# PowerSocket2.net
KiCad netlist of a schematic drawn in EAGLE
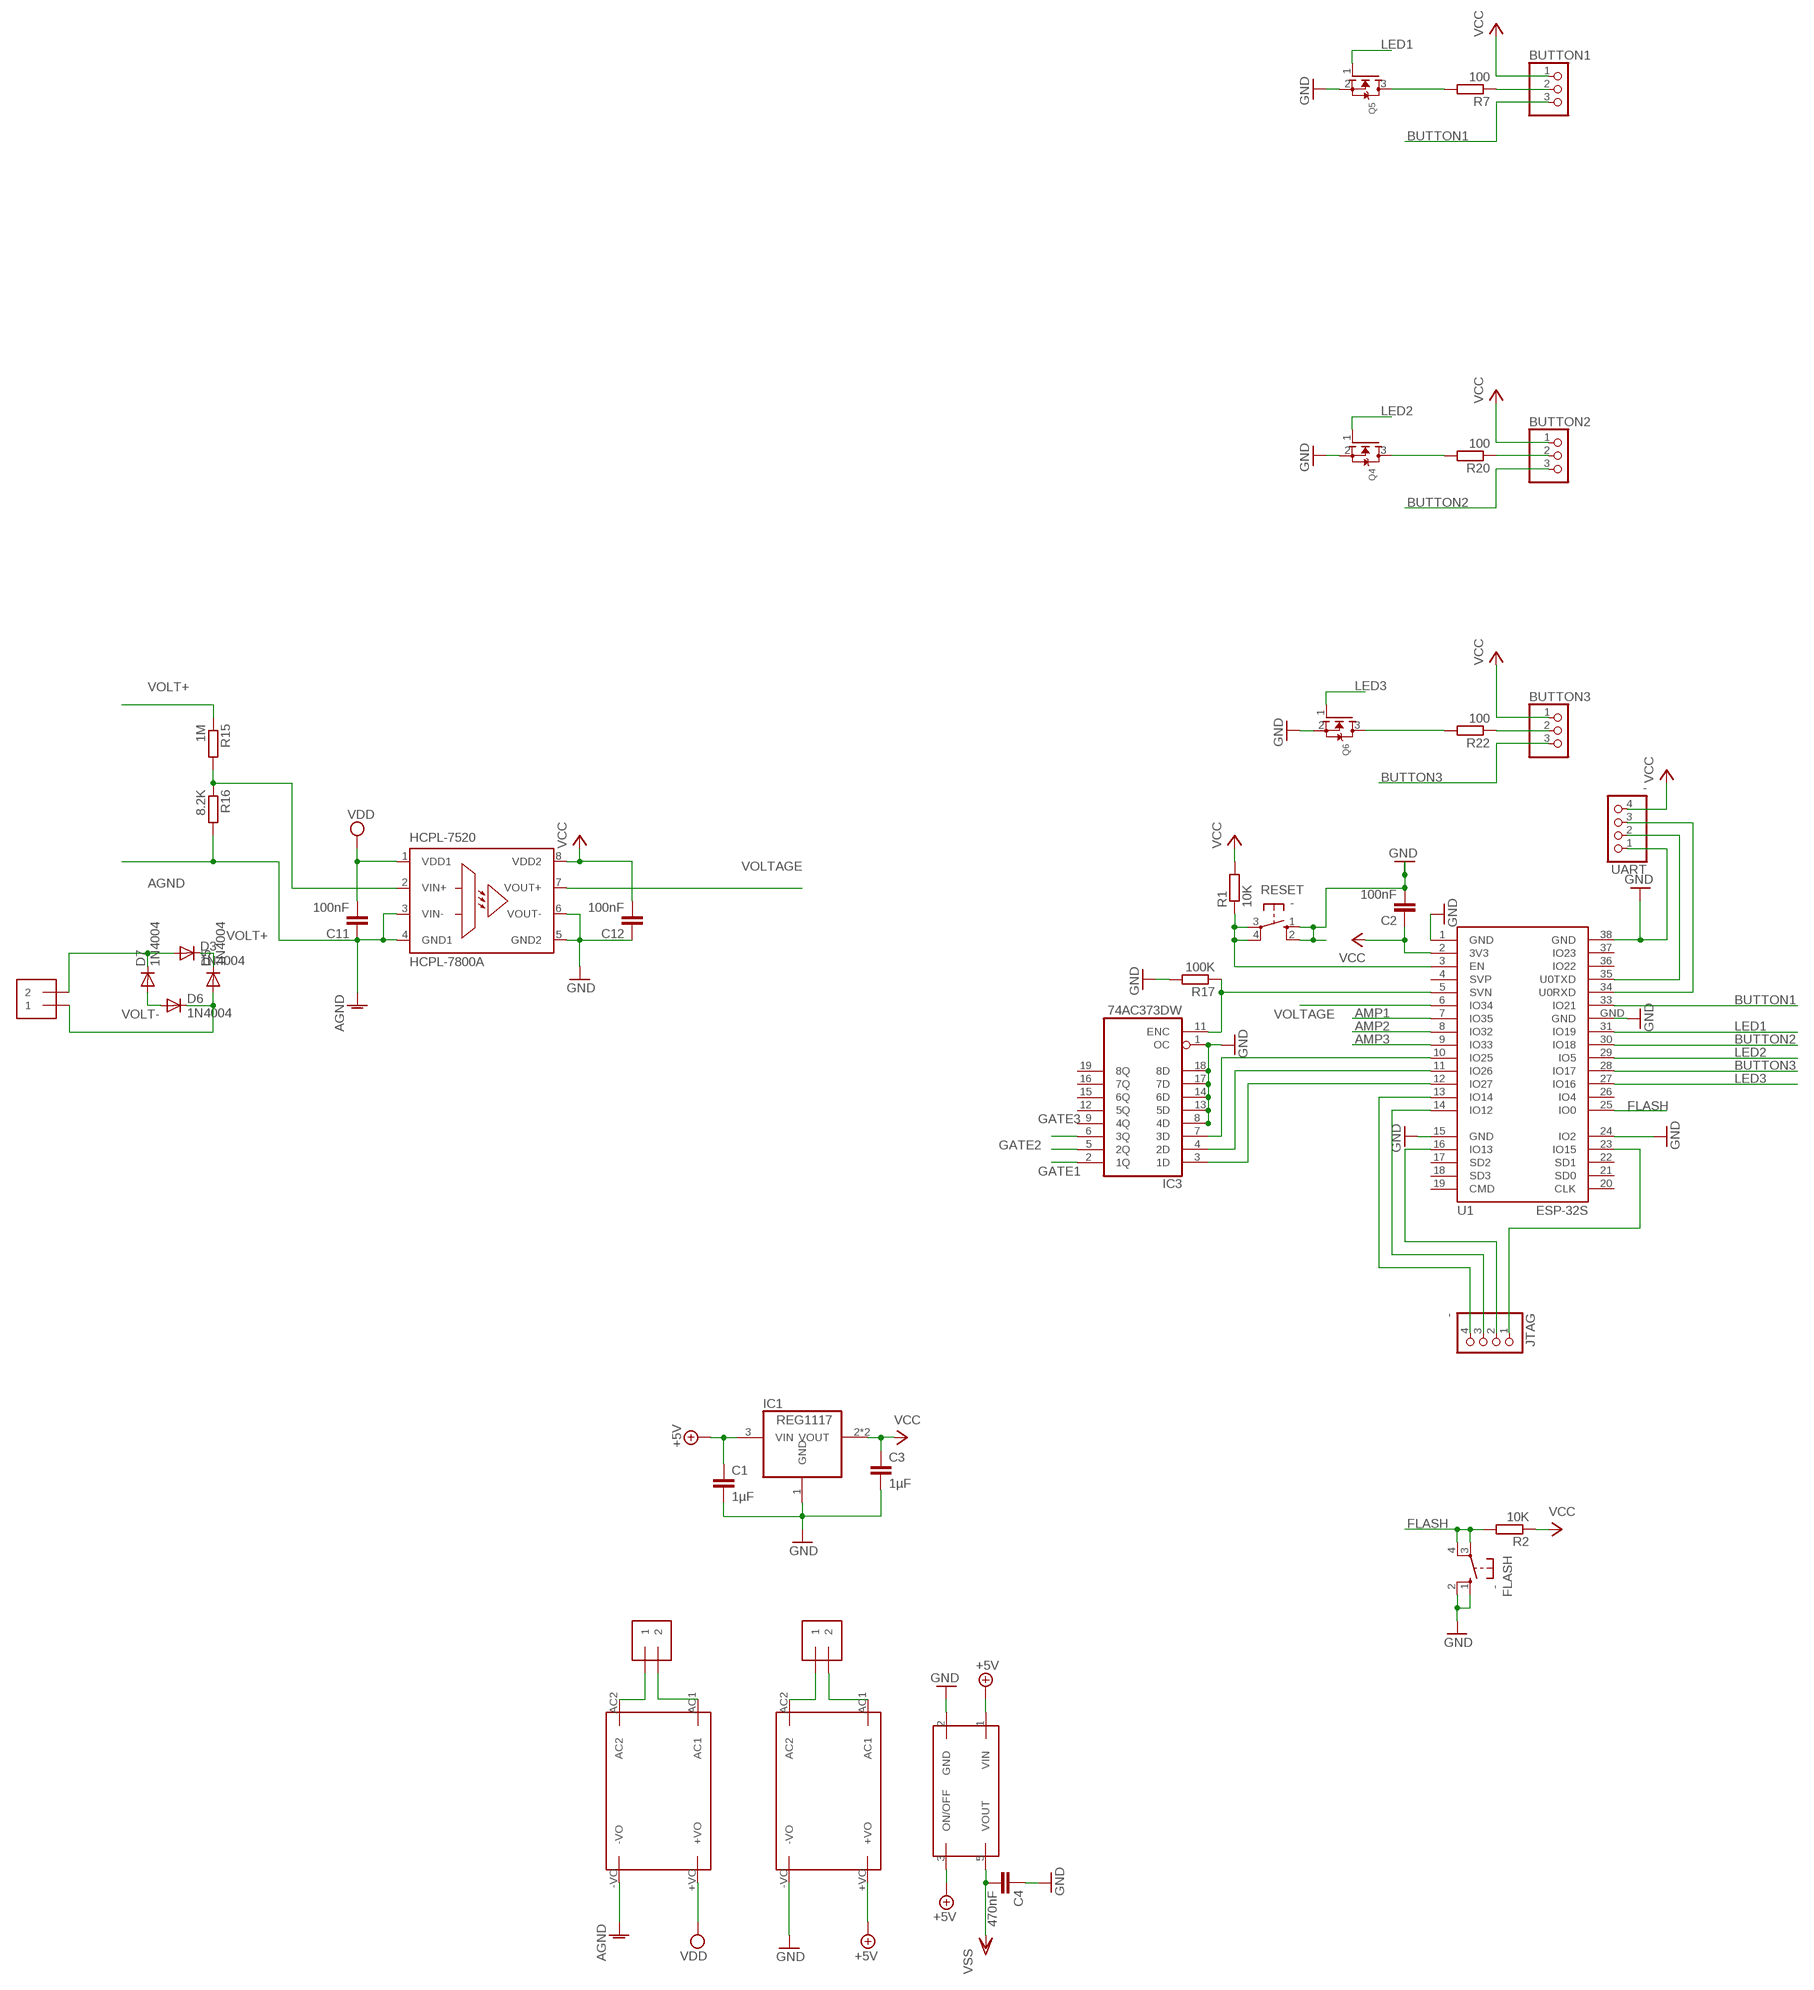
[diagram p0: schematic, sheet 1, part 1 of 2]
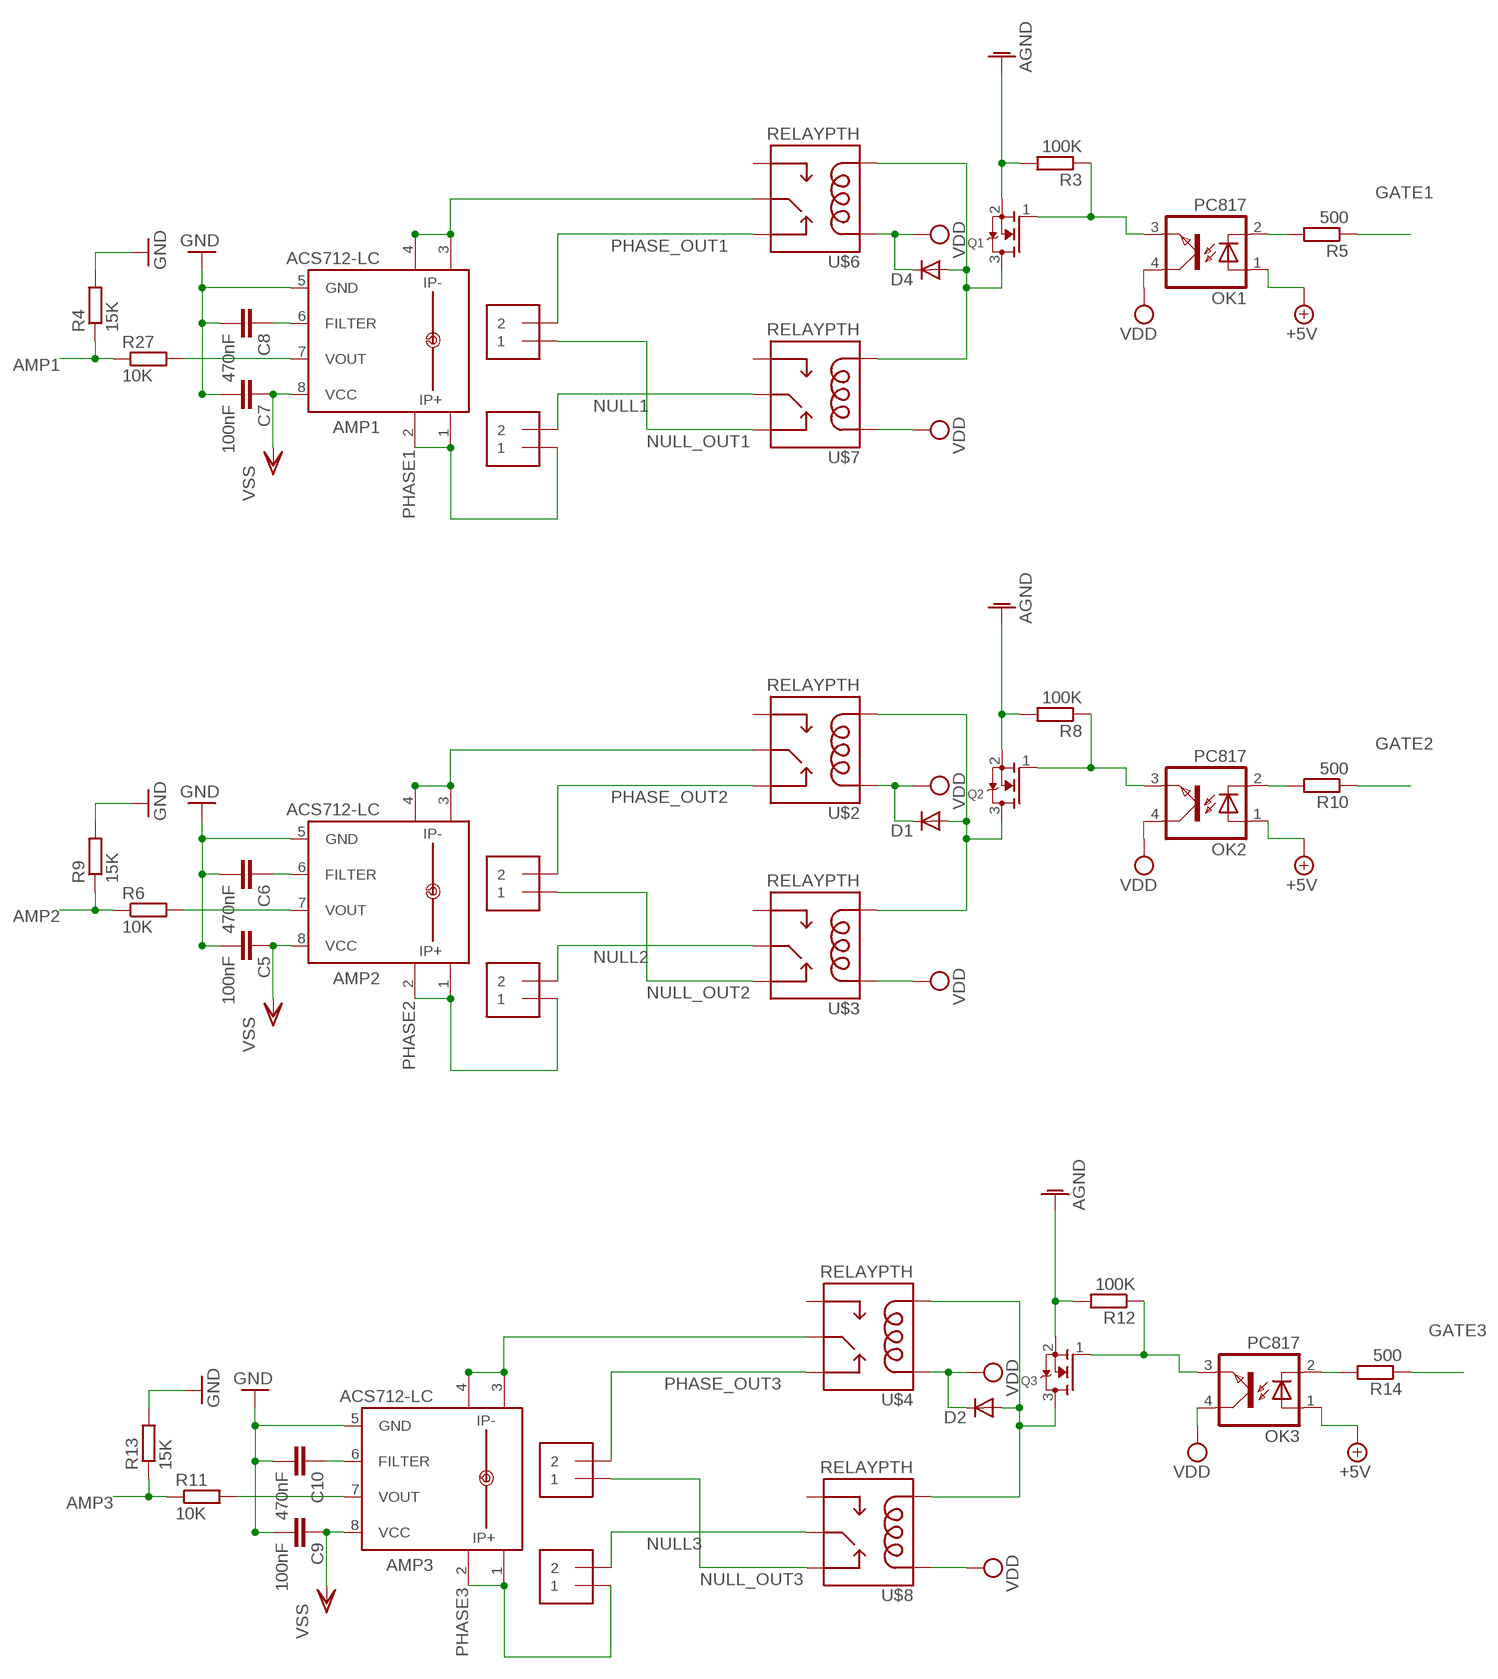
[diagram p1: schematic, sheet 1, part 2 of 2]

(export (version "E")
  (design (tool "Eeschema 10.0.6"))
  (components
    (comp (ref "4.5V_REG")
      (value "S1112")
      (footprint "eagle-import:SOT23-5")
      (libsource (lib "eagle-import") (part "S1112"))
    )
    (comp (ref "AMP1")
      (value "ACS712-LC")
      (footprint "eagle-import:SOIC8")
      (libsource (lib "eagle-import") (part "ACS712-LC"))
    )
    (comp (ref "AMP2")
      (value "ACS712-LC")
      (footprint "eagle-import:SOIC8")
      (libsource (lib "eagle-import") (part "ACS712-LC"))
    )
    (comp (ref "AMP3")
      (value "ACS712-LC")
      (footprint "eagle-import:SOIC8")
      (libsource (lib "eagle-import") (part "ACS712-LC"))
    )
    (comp (ref "BUTTON1")
      (value "PINHD-1X3")
      (footprint "eagle-import:1X03")
      (libsource (lib "eagle-import") (part "PINHD-1X3"))
    )
    (comp (ref "BUTTON2")
      (value "PINHD-1X3")
      (footprint "eagle-import:1X03")
      (libsource (lib "eagle-import") (part "PINHD-1X3"))
    )
    (comp (ref "BUTTON3")
      (value "PINHD-1X3")
      (footprint "eagle-import:1X03")
      (libsource (lib "eagle-import") (part "PINHD-1X3"))
    )
    (comp (ref "C1")
      (value "1µF")
      (footprint "eagle-import:C025-024X044")
      (libsource (lib "eagle-import") (part "C-EU025-024X044"))
    )
    (comp (ref "C2")
      (value "100nF")
      (footprint "eagle-import:C1206")
      (libsource (lib "eagle-import") (part "C-EUC1206"))
    )
    (comp (ref "C3")
      (value "1µF")
      (footprint "eagle-import:C025-024X044")
      (libsource (lib "eagle-import") (part "C-EU025-024X044"))
    )
    (comp (ref "C4")
      (value "470nF")
      (footprint "eagle-import:C0805")
      (libsource (lib "eagle-import") (part "C-EUC0805"))
    )
    (comp (ref "C5")
      (value "100nF")
      (footprint "eagle-import:C0805")
      (libsource (lib "eagle-import") (part "C-EUC0805"))
    )
    (comp (ref "C6")
      (value "470nF")
      (footprint "eagle-import:C0805")
      (libsource (lib "eagle-import") (part "C-EUC0805"))
    )
    (comp (ref "C7")
      (value "100nF")
      (footprint "eagle-import:C0805")
      (libsource (lib "eagle-import") (part "C-EUC0805"))
    )
    (comp (ref "C8")
      (value "470nF")
      (footprint "eagle-import:C0805")
      (libsource (lib "eagle-import") (part "C-EUC0805"))
    )
    (comp (ref "C9")
      (value "100nF")
      (footprint "eagle-import:C0805")
      (libsource (lib "eagle-import") (part "C-EUC0805"))
    )
    (comp (ref "C10")
      (value "470nF")
      (footprint "eagle-import:C0805")
      (libsource (lib "eagle-import") (part "C-EUC0805"))
    )
    (comp (ref "C11")
      (value "100nF")
      (footprint "eagle-import:C1206")
      (libsource (lib "eagle-import") (part "C-EUC1206"))
    )
    (comp (ref "C12")
      (value "100nF")
      (footprint "eagle-import:C1206")
      (libsource (lib "eagle-import") (part "C-EUC1206"))
    )
    (comp (ref "D1")
      (value "DIODE-DO-214AC")
      (footprint "eagle-import:DO-214AC")
      (libsource (lib "eagle-import") (part "DIODE-DO-214AC"))
    )
    (comp (ref "D2")
      (value "DIODE-DO-214AC")
      (footprint "eagle-import:DO-214AC")
      (libsource (lib "eagle-import") (part "DIODE-DO-214AC"))
    )
    (comp (ref "D3")
      (value "1N4004")
      (footprint "eagle-import:DO41-10")
      (libsource (lib "eagle-import") (part "1N4004"))
    )
    (comp (ref "D4")
      (value "DIODE-DO-214AC")
      (footprint "eagle-import:DO-214AC")
      (libsource (lib "eagle-import") (part "DIODE-DO-214AC"))
    )
    (comp (ref "D5")
      (value "1N4004")
      (footprint "eagle-import:DO41-10")
      (libsource (lib "eagle-import") (part "1N4004"))
    )
    (comp (ref "D6")
      (value "1N4004")
      (footprint "eagle-import:DO41-10")
      (libsource (lib "eagle-import") (part "1N4004"))
    )
    (comp (ref "D7")
      (value "1N4004")
      (footprint "eagle-import:DO41-10")
      (libsource (lib "eagle-import") (part "1N4004"))
    )
    (comp (ref "FLASH")
      (value "-")
      (footprint "eagle-import:B3F-10XX")
      (fields (field (name "MPN") "B3F-1000"))
      (libsource (lib "eagle-import") (part "10-XX"))
    )
    (comp (ref "HCPL-7520")
      (value "HCPL-7800A")
      (footprint "eagle-import:DIP8")
      (fields (field (name "MF") "AGILENT TECHNOLOGIES") (field (name "MPN") "HCPL-7800A-000E"))
      (libsource (lib "eagle-import") (part "HCPL-7800A"))
    )
    (comp (ref "IC1")
      (value "REG1117")
      (footprint "eagle-import:SOT223")
      (libsource (lib "eagle-import") (part "REG1117"))
    )
    (comp (ref "IC3")
      (value "74AC373DW")
      (footprint "eagle-import:SO20W")
      (libsource (lib "eagle-import") (part "74373DWAC"))
    )
    (comp (ref "J1")
      (value "1X2-3.5MM")
      (footprint "eagle-import:1X2-3.5MM")
      (libsource (lib "eagle-import") (part "1X2-3.5MM"))
    )
    (comp (ref "J2")
      (value "1X2-3.5MM")
      (footprint "eagle-import:1X2-3.5MM")
      (libsource (lib "eagle-import") (part "1X2-3.5MM"))
    )
    (comp (ref "J3")
      (value "1X2-3.5MM")
      (footprint "eagle-import:1X2-3.5MM")
      (libsource (lib "eagle-import") (part "1X2-3.5MM"))
    )
    (comp (ref "J4")
      (value "1X2-3.5MM")
      (footprint "eagle-import:1X2-3.5MM")
      (libsource (lib "eagle-import") (part "1X2-3.5MM"))
    )
    (comp (ref "J5")
      (value "1X2-3.5MM")
      (footprint "eagle-import:1X2-3.5MM")
      (libsource (lib "eagle-import") (part "1X2-3.5MM"))
    )
    (comp (ref "J6")
      (value "1X2-3.5MM")
      (footprint "eagle-import:1X2-3.5MM")
      (libsource (lib "eagle-import") (part "1X2-3.5MM"))
    )
    (comp (ref "J7")
      (value "1X2-3.5MM")
      (footprint "eagle-import:1X2-3.5MM")
      (libsource (lib "eagle-import") (part "1X2-3.5MM"))
    )
    (comp (ref "J8")
      (value "1X2-3.5MM")
      (footprint "eagle-import:1X2-3.5MM")
      (libsource (lib "eagle-import") (part "1X2-3.5MM"))
    )
    (comp (ref "J9")
      (value "1X2-3.5MM")
      (footprint "eagle-import:1X2-3.5MM")
      (libsource (lib "eagle-import") (part "1X2-3.5MM"))
    )
    (comp (ref "JTAG")
      (value "-")
      (footprint "eagle-import:1X04")
      (libsource (lib "eagle-import") (part "PINHD-1X4"))
    )
    (comp (ref "OK1")
      (value "PC817")
      (footprint "eagle-import:DIL04")
      (fields (field (name "MPN") "PC817X4J000F"))
      (libsource (lib "eagle-import") (part "PC817"))
    )
    (comp (ref "OK2")
      (value "PC817")
      (footprint "eagle-import:DIL04")
      (fields (field (name "MPN") "PC817X4J000F"))
      (libsource (lib "eagle-import") (part "PC817"))
    )
    (comp (ref "OK3")
      (value "PC817")
      (footprint "eagle-import:DIL04")
      (fields (field (name "MPN") "PC817X4J000F"))
      (libsource (lib "eagle-import") (part "PC817"))
    )
    (comp (ref "Q1")
      (value "MOSFET-NREFLOW")
      (footprint "eagle-import:SOT23")
      (libsource (lib "eagle-import") (part "MOSFET-NREFLOW"))
    )
    (comp (ref "Q2")
      (value "MOSFET-NREFLOW")
      (footprint "eagle-import:SOT23")
      (libsource (lib "eagle-import") (part "MOSFET-NREFLOW"))
    )
    (comp (ref "Q3")
      (value "MOSFET-NREFLOW")
      (footprint "eagle-import:SOT23")
      (libsource (lib "eagle-import") (part "MOSFET-NREFLOW"))
    )
    (comp (ref "Q4")
      (value "MOSFET-NREFLOW")
      (footprint "eagle-import:SOT23")
      (libsource (lib "eagle-import") (part "MOSFET-NREFLOW"))
    )
    (comp (ref "Q5")
      (value "MOSFET-NREFLOW")
      (footprint "eagle-import:SOT23")
      (libsource (lib "eagle-import") (part "MOSFET-NREFLOW"))
    )
    (comp (ref "Q6")
      (value "MOSFET-NREFLOW")
      (footprint "eagle-import:SOT23")
      (libsource (lib "eagle-import") (part "MOSFET-NREFLOW"))
    )
    (comp (ref "R1")
      (value "10K")
      (footprint "eagle-import:R0805")
      (libsource (lib "eagle-import") (part "R-EU_R0805"))
    )
    (comp (ref "R2")
      (value "10K")
      (footprint "eagle-import:R0805")
      (libsource (lib "eagle-import") (part "R-EU_R0805"))
    )
    (comp (ref "R3")
      (value "100K")
      (footprint "eagle-import:R0805")
      (libsource (lib "eagle-import") (part "R-EU_R0805"))
    )
    (comp (ref "R4")
      (value "15K")
      (footprint "eagle-import:R0805")
      (libsource (lib "eagle-import") (part "R-EU_R0805"))
    )
    (comp (ref "R5")
      (value "500")
      (footprint "eagle-import:R0805")
      (libsource (lib "eagle-import") (part "R-EU_R0805"))
    )
    (comp (ref "R6")
      (value "10K")
      (footprint "eagle-import:R0805")
      (libsource (lib "eagle-import") (part "R-EU_R0805"))
    )
    (comp (ref "R7")
      (value "100")
      (footprint "eagle-import:R0805")
      (libsource (lib "eagle-import") (part "R-EU_R0805"))
    )
    (comp (ref "R8")
      (value "100K")
      (footprint "eagle-import:R0805")
      (libsource (lib "eagle-import") (part "R-EU_R0805"))
    )
    (comp (ref "R9")
      (value "15K")
      (footprint "eagle-import:R0805")
      (libsource (lib "eagle-import") (part "R-EU_R0805"))
    )
    (comp (ref "R10")
      (value "500")
      (footprint "eagle-import:R0805")
      (libsource (lib "eagle-import") (part "R-EU_R0805"))
    )
    (comp (ref "R11")
      (value "10K")
      (footprint "eagle-import:R0805")
      (libsource (lib "eagle-import") (part "R-EU_R0805"))
    )
    (comp (ref "R12")
      (value "100K")
      (footprint "eagle-import:R0805")
      (libsource (lib "eagle-import") (part "R-EU_R0805"))
    )
    (comp (ref "R13")
      (value "15K")
      (footprint "eagle-import:R0805")
      (libsource (lib "eagle-import") (part "R-EU_R0805"))
    )
    (comp (ref "R14")
      (value "500")
      (footprint "eagle-import:R0805")
      (libsource (lib "eagle-import") (part "R-EU_R0805"))
    )
    (comp (ref "R15")
      (value "1M")
      (footprint "eagle-import:0207_10")
      (libsource (lib "eagle-import") (part "resistor_R-EU_0207/10"))
    )
    (comp (ref "R16")
      (value "8.2K")
      (footprint "eagle-import:0207_10")
      (libsource (lib "eagle-import") (part "resistor_R-EU_0207/10"))
    )
    (comp (ref "R17")
      (value "100K")
      (footprint "eagle-import:R0805")
      (libsource (lib "eagle-import") (part "R-EU_R0805"))
    )
    (comp (ref "R20")
      (value "100")
      (footprint "eagle-import:R0805")
      (libsource (lib "eagle-import") (part "R-EU_R0805"))
    )
    (comp (ref "R22")
      (value "100")
      (footprint "eagle-import:R0805")
      (libsource (lib "eagle-import") (part "R-EU_R0805"))
    )
    (comp (ref "R27")
      (value "10K")
      (footprint "eagle-import:R0805")
      (libsource (lib "eagle-import") (part "R-EU_R0805"))
    )
    (comp (ref "RESET")
      (value "-")
      (footprint "eagle-import:B3F-10XX")
      (fields (field (name "MPN") "B3F-1000"))
      (libsource (lib "eagle-import") (part "10-XX"))
    )
    (comp (ref "U$1")
      (value "HLK-PM03")
      (footprint "eagle-import:HLK-PM03")
      (libsource (lib "eagle-import") (part "HLK-PM03"))
    )
    (comp (ref "U$2")
      (value "RELAYPTH")
      (footprint "eagle-import:SRD-05VDC-SL-C")
      (libsource (lib "eagle-import") (part "RELAYPTH"))
    )
    (comp (ref "U$3")
      (value "RELAYPTH")
      (footprint "eagle-import:SRD-05VDC-SL-C")
      (libsource (lib "eagle-import") (part "RELAYPTH"))
    )
    (comp (ref "U$4")
      (value "RELAYPTH")
      (footprint "eagle-import:SRD-05VDC-SL-C")
      (libsource (lib "eagle-import") (part "RELAYPTH"))
    )
    (comp (ref "U$5")
      (value "HLK-PM03")
      (footprint "eagle-import:HLK-PM03")
      (libsource (lib "eagle-import") (part "HLK-PM03"))
    )
    (comp (ref "U$6")
      (value "RELAYPTH")
      (footprint "eagle-import:SRD-05VDC-SL-C")
      (libsource (lib "eagle-import") (part "RELAYPTH"))
    )
    (comp (ref "U$7")
      (value "RELAYPTH")
      (footprint "eagle-import:SRD-05VDC-SL-C")
      (libsource (lib "eagle-import") (part "RELAYPTH"))
    )
    (comp (ref "U$8")
      (value "RELAYPTH")
      (footprint "eagle-import:SRD-05VDC-SL-C")
      (libsource (lib "eagle-import") (part "RELAYPTH"))
    )
    (comp (ref "U1")
      (value "ESP-32S")
      (footprint "eagle-import:ESP-32S")
      (libsource (lib "eagle-import") (part "ESP-32S"))
    )
    (comp (ref "UART")
      (value "-")
      (footprint "eagle-import:1X04")
      (libsource (lib "eagle-import") (part "PINHD-1X4"))
    )
  )
  (nets
    (net (code "1") (name "+5V") (class "Default")
      (node (ref "4.5V_REG") (pin "1") (pinfunction "VIN_1") (pintype "power_in"))
      (node (ref "4.5V_REG") (pin "3") (pinfunction "ON/OFF_3") (pintype "input"))
      (node (ref "C1") (pin "1") (pinfunction "1_1") (pintype "passive"))
      (node (ref "IC1") (pin "3") (pinfunction "VIN_3") (pintype "input"))
      (node (ref "OK1") (pin "1") (pinfunction "A_1") (pintype "passive"))
      (node (ref "OK2") (pin "1") (pinfunction "A_1") (pintype "passive"))
      (node (ref "OK3") (pin "1") (pinfunction "A_1") (pintype "passive"))
      (node (ref "U$1") (pin "+VO") (pinfunction "+VO_+VO") (pintype "bidirectional"))
    )
    (net (code "2") (name "/AMP1") (class "Default")
      (node (ref "R27") (pin "1") (pinfunction "1_1") (pintype "passive"))
      (node (ref "R4") (pin "1") (pinfunction "1_1") (pintype "passive"))
      (node (ref "U1") (pin "7") (pinfunction "IO35_7") (pintype "bidirectional"))
    )
    (net (code "3") (name "/AMP2") (class "Default")
      (node (ref "R6") (pin "1") (pinfunction "1_1") (pintype "passive"))
      (node (ref "R9") (pin "1") (pinfunction "1_1") (pintype "passive"))
      (node (ref "U1") (pin "8") (pinfunction "IO32_8") (pintype "bidirectional"))
    )
    (net (code "4") (name "/AMP3") (class "Default")
      (node (ref "R11") (pin "1") (pinfunction "1_1") (pintype "passive"))
      (node (ref "R13") (pin "1") (pinfunction "1_1") (pintype "passive"))
      (node (ref "U1") (pin "9") (pinfunction "IO33_9") (pintype "bidirectional"))
    )
    (net (code "5") (name "/BUTTON1") (class "Default")
      (node (ref "BUTTON1") (pin "3") (pinfunction "3_3") (pintype "passive"))
      (node (ref "U1") (pin "33") (pinfunction "IO21_33") (pintype "bidirectional"))
    )
    (net (code "6") (name "/BUTTON2") (class "Default")
      (node (ref "BUTTON2") (pin "3") (pinfunction "3_3") (pintype "passive"))
      (node (ref "U1") (pin "30") (pinfunction "IO18_30") (pintype "bidirectional"))
    )
    (net (code "7") (name "/BUTTON3") (class "Default")
      (node (ref "BUTTON3") (pin "3") (pinfunction "3_3") (pintype "passive"))
      (node (ref "U1") (pin "28") (pinfunction "IO17_28") (pintype "bidirectional"))
    )
    (net (code "8") (name "/FLASH") (class "Default")
      (node (ref "FLASH") (pin "3") (pinfunction "P_3") (pintype "passive"))
      (node (ref "FLASH") (pin "4") (pinfunction "P1_4") (pintype "passive"))
      (node (ref "R2") (pin "2") (pinfunction "2_2") (pintype "passive"))
      (node (ref "U1") (pin "25") (pinfunction "IO0_25") (pintype "bidirectional"))
    )
    (net (code "9") (name "/GATE1") (class "Default")
      (node (ref "IC3") (pin "2") (pinfunction "1Q_2") (pintype "tri_state"))
      (node (ref "R5") (pin "1") (pinfunction "1_1") (pintype "passive"))
    )
    (net (code "10") (name "/GATE2") (class "Default")
      (node (ref "IC3") (pin "5") (pinfunction "2Q_5") (pintype "tri_state"))
      (node (ref "R10") (pin "1") (pinfunction "1_1") (pintype "passive"))
    )
    (net (code "11") (name "/GATE3") (class "Default")
      (node (ref "IC3") (pin "6") (pinfunction "3Q_6") (pintype "tri_state"))
      (node (ref "R14") (pin "1") (pinfunction "1_1") (pintype "passive"))
    )
    (net (code "12") (name "/LED1") (class "Default")
      (node (ref "Q5") (pin "1") (pinfunction "G_1") (pintype "bidirectional"))
      (node (ref "U1") (pin "31") (pinfunction "IO19_31") (pintype "bidirectional"))
    )
    (net (code "13") (name "/LED2") (class "Default")
      (node (ref "Q4") (pin "1") (pinfunction "G_1") (pintype "bidirectional"))
      (node (ref "U1") (pin "29") (pinfunction "IO5_29") (pintype "bidirectional"))
    )
    (net (code "14") (name "/LED3") (class "Default")
      (node (ref "Q6") (pin "1") (pinfunction "G_1") (pintype "bidirectional"))
      (node (ref "U1") (pin "27") (pinfunction "IO16_27") (pintype "bidirectional"))
    )
    (net (code "15") (name "/NULL1") (class "Default")
      (node (ref "J2") (pin "2") (pinfunction "2_2") (pintype "passive"))
      (node (ref "U$7") (pin "SWCOMMON") (pinfunction "SWCOMMON_SWCOMMON") (pintype "bidirectional"))
    )
    (net (code "16") (name "/NULL2") (class "Default")
      (node (ref "J6") (pin "2") (pinfunction "2_2") (pintype "passive"))
      (node (ref "U$3") (pin "SWCOMMON") (pinfunction "SWCOMMON_SWCOMMON") (pintype "bidirectional"))
    )
    (net (code "17") (name "/NULL3") (class "Default")
      (node (ref "J8") (pin "2") (pinfunction "2_2") (pintype "passive"))
      (node (ref "U$8") (pin "SWCOMMON") (pinfunction "SWCOMMON_SWCOMMON") (pintype "bidirectional"))
    )
    (net (code "18") (name "/NULL_OUT1") (class "Default")
      (node (ref "J1") (pin "1") (pinfunction "1_1") (pintype "passive"))
      (node (ref "U$7") (pin "SWCLOSED") (pinfunction "SWCLOSE_SWCLOSED") (pintype "bidirectional"))
    )
    (net (code "19") (name "/NULL_OUT2") (class "Default")
      (node (ref "J5") (pin "1") (pinfunction "1_1") (pintype "passive"))
      (node (ref "U$3") (pin "SWCLOSED") (pinfunction "SWCLOSE_SWCLOSED") (pintype "bidirectional"))
    )
    (net (code "20") (name "/NULL_OUT3") (class "Default")
      (node (ref "J7") (pin "1") (pinfunction "1_1") (pintype "passive"))
      (node (ref "U$8") (pin "SWCLOSED") (pinfunction "SWCLOSE_SWCLOSED") (pintype "bidirectional"))
    )
    (net (code "21") (name "/PHASE1") (class "Default")
      (node (ref "AMP1") (pin "1") (pinfunction "IP+_1") (pintype "passive"))
      (node (ref "AMP1") (pin "2") (pinfunction "IP+1_2") (pintype "passive"))
      (node (ref "J2") (pin "1") (pinfunction "1_1") (pintype "passive"))
    )
    (net (code "22") (name "/PHASE2") (class "Default")
      (node (ref "AMP2") (pin "1") (pinfunction "IP+_1") (pintype "passive"))
      (node (ref "AMP2") (pin "2") (pinfunction "IP+1_2") (pintype "passive"))
      (node (ref "J6") (pin "1") (pinfunction "1_1") (pintype "passive"))
    )
    (net (code "23") (name "/PHASE3") (class "Default")
      (node (ref "AMP3") (pin "1") (pinfunction "IP+_1") (pintype "passive"))
      (node (ref "AMP3") (pin "2") (pinfunction "IP+1_2") (pintype "passive"))
      (node (ref "J8") (pin "1") (pinfunction "1_1") (pintype "passive"))
    )
    (net (code "24") (name "/PHASE_OUT1") (class "Default")
      (node (ref "J1") (pin "2") (pinfunction "2_2") (pintype "passive"))
      (node (ref "U$6") (pin "SWCLOSED") (pinfunction "SWCLOSE_SWCLOSED") (pintype "bidirectional"))
    )
    (net (code "25") (name "/PHASE_OUT2") (class "Default")
      (node (ref "J5") (pin "2") (pinfunction "2_2") (pintype "passive"))
      (node (ref "U$2") (pin "SWCLOSED") (pinfunction "SWCLOSE_SWCLOSED") (pintype "bidirectional"))
    )
    (net (code "26") (name "/PHASE_OUT3") (class "Default")
      (node (ref "J7") (pin "2") (pinfunction "2_2") (pintype "passive"))
      (node (ref "U$4") (pin "SWCLOSED") (pinfunction "SWCLOSE_SWCLOSED") (pintype "bidirectional"))
    )
    (net (code "27") (name "/VOLT+") (class "Default")
      (node (ref "D3") (pin "C") (pinfunction "C_C") (pintype "passive"))
      (node (ref "D5") (pin "C") (pinfunction "C_C") (pintype "passive"))
      (node (ref "R15") (pin "1") (pinfunction "1_1") (pintype "passive"))
    )
    (net (code "28") (name "/VOLT-") (class "Default")
      (node (ref "D6") (pin "A") (pinfunction "A_A") (pintype "passive"))
      (node (ref "D7") (pin "A") (pinfunction "A_A") (pintype "passive"))
    )
    (net (code "29") (name "/VOLTAGE") (class "Default")
      (node (ref "HCPL-7520") (pin "7") (pinfunction "VOUT+_7") (pintype "power_in"))
      (node (ref "U1") (pin "6") (pinfunction "IO34_6") (pintype "bidirectional"))
    )
    (net (code "30") (name "AGND") (class "Default")
      (node (ref "C11") (pin "1") (pinfunction "1_1") (pintype "passive"))
      (node (ref "HCPL-7520") (pin "3") (pinfunction "VIN-_3") (pintype "power_in"))
      (node (ref "HCPL-7520") (pin "4") (pinfunction "GND1_4") (pintype "power_in"))
      (node (ref "Q1") (pin "2") (pinfunction "S_2") (pintype "bidirectional"))
      (node (ref "Q2") (pin "2") (pinfunction "S_2") (pintype "bidirectional"))
      (node (ref "Q3") (pin "2") (pinfunction "S_2") (pintype "bidirectional"))
      (node (ref "R12") (pin "2") (pinfunction "2_2") (pintype "passive"))
      (node (ref "R16") (pin "2") (pinfunction "2_2") (pintype "passive"))
      (node (ref "R3") (pin "2") (pinfunction "2_2") (pintype "passive"))
      (node (ref "R8") (pin "2") (pinfunction "2_2") (pintype "passive"))
      (node (ref "U$5") (pin "-VO") (pinfunction "-VO_-VO") (pintype "bidirectional"))
    )
    (net (code "31") (name "GND") (class "Default")
      (node (ref "4.5V_REG") (pin "2") (pinfunction "GND_2") (pintype "power_in"))
      (node (ref "AMP1") (pin "5") (pinfunction "GND_5") (pintype "power_in"))
      (node (ref "AMP2") (pin "5") (pinfunction "GND_5") (pintype "power_in"))
      (node (ref "AMP3") (pin "5") (pinfunction "GND_5") (pintype "power_in"))
      (node (ref "C1") (pin "2") (pinfunction "2_2") (pintype "passive"))
      (node (ref "C10") (pin "2") (pinfunction "2_2") (pintype "passive"))
      (node (ref "C12") (pin "1") (pinfunction "1_1") (pintype "passive"))
      (node (ref "C2") (pin "2") (pinfunction "2_2") (pintype "passive"))
      (node (ref "C3") (pin "2") (pinfunction "2_2") (pintype "passive"))
      (node (ref "C4") (pin "1") (pinfunction "1_1") (pintype "passive"))
      (node (ref "C5") (pin "2") (pinfunction "2_2") (pintype "passive"))
      (node (ref "C6") (pin "2") (pinfunction "2_2") (pintype "passive"))
      (node (ref "C7") (pin "2") (pinfunction "2_2") (pintype "passive"))
      (node (ref "C8") (pin "2") (pinfunction "2_2") (pintype "passive"))
      (node (ref "C9") (pin "2") (pinfunction "2_2") (pintype "passive"))
      (node (ref "FLASH") (pin "1") (pinfunction "S_1") (pintype "passive"))
      (node (ref "FLASH") (pin "2") (pinfunction "S1_2") (pintype "passive"))
      (node (ref "HCPL-7520") (pin "5") (pinfunction "GND2_5") (pintype "power_in"))
      (node (ref "HCPL-7520") (pin "6") (pinfunction "VOUT-_6") (pintype "power_in"))
      (node (ref "IC1") (pin "1") (pinfunction "GND_1") (pintype "power_in"))
      (node (ref "IC3") (pin "1") (pinfunction "OC_1") (pintype "input"))
      (node (ref "IC3") (pin "13") (pinfunction "5D_13") (pintype "input"))
      (node (ref "IC3") (pin "14") (pinfunction "6D_14") (pintype "input"))
      (node (ref "IC3") (pin "17") (pinfunction "7D_17") (pintype "input"))
      (node (ref "IC3") (pin "18") (pinfunction "8D_18") (pintype "input"))
      (node (ref "IC3") (pin "8") (pinfunction "4D_8") (pintype "input"))
      (node (ref "Q4") (pin "2") (pinfunction "S_2") (pintype "bidirectional"))
      (node (ref "Q5") (pin "2") (pinfunction "S_2") (pintype "bidirectional"))
      (node (ref "Q6") (pin "2") (pinfunction "S_2") (pintype "bidirectional"))
      (node (ref "R13") (pin "2") (pinfunction "2_2") (pintype "passive"))
      (node (ref "R17") (pin "2") (pinfunction "2_2") (pintype "passive"))
      (node (ref "R4") (pin "2") (pinfunction "2_2") (pintype "passive"))
      (node (ref "R9") (pin "2") (pinfunction "2_2") (pintype "passive"))
      (node (ref "RESET") (pin "1") (pinfunction "S_1") (pintype "passive"))
      (node (ref "RESET") (pin "2") (pinfunction "S1_2") (pintype "passive"))
      (node (ref "U$1") (pin "-VO") (pinfunction "-VO_-VO") (pintype "bidirectional"))
      (node (ref "U1") (pin "1") (pinfunction "GND_1") (pintype "power_in"))
      (node (ref "U1") (pin "15") (pinfunction "GND_15") (pintype "power_in"))
      (node (ref "U1") (pin "24") (pinfunction "IO2_24") (pintype "bidirectional"))
      (node (ref "U1") (pin "38") (pinfunction "GND_38") (pintype "power_in"))
      (node (ref "U1") (pin "GND") (pinfunction "GND_GND") (pintype "power_in"))
      (node (ref "UART") (pin "1") (pinfunction "1_1") (pintype "passive"))
    )
    (net (code "32") (name "Net-(AMP1-FILTER)") (class "Default")
      (node (ref "AMP1") (pin "6") (pinfunction "FILTER_6") (pintype "bidirectional"))
      (node (ref "C8") (pin "1") (pinfunction "1_1") (pintype "passive"))
    )
    (net (code "33") (name "Net-(AMP1-IP-)") (class "Default")
      (node (ref "AMP1") (pin "3") (pinfunction "IP-_3") (pintype "passive"))
      (node (ref "AMP1") (pin "4") (pinfunction "IP-1_4") (pintype "passive"))
      (node (ref "U$6") (pin "SWCOMMON") (pinfunction "SWCOMMON_SWCOMMON") (pintype "bidirectional"))
    )
    (net (code "34") (name "Net-(AMP1-VOUT)") (class "Default")
      (node (ref "AMP1") (pin "7") (pinfunction "VOUT_7") (pintype "output"))
      (node (ref "R27") (pin "2") (pinfunction "2_2") (pintype "passive"))
    )
    (net (code "35") (name "Net-(AMP2-FILTER)") (class "Default")
      (node (ref "AMP2") (pin "6") (pinfunction "FILTER_6") (pintype "bidirectional"))
      (node (ref "C6") (pin "1") (pinfunction "1_1") (pintype "passive"))
    )
    (net (code "36") (name "Net-(AMP2-IP-)") (class "Default")
      (node (ref "AMP2") (pin "3") (pinfunction "IP-_3") (pintype "passive"))
      (node (ref "AMP2") (pin "4") (pinfunction "IP-1_4") (pintype "passive"))
      (node (ref "U$2") (pin "SWCOMMON") (pinfunction "SWCOMMON_SWCOMMON") (pintype "bidirectional"))
    )
    (net (code "37") (name "Net-(AMP2-VOUT)") (class "Default")
      (node (ref "AMP2") (pin "7") (pinfunction "VOUT_7") (pintype "output"))
      (node (ref "R6") (pin "2") (pinfunction "2_2") (pintype "passive"))
    )
    (net (code "38") (name "Net-(AMP3-FILTER)") (class "Default")
      (node (ref "AMP3") (pin "6") (pinfunction "FILTER_6") (pintype "bidirectional"))
      (node (ref "C10") (pin "1") (pinfunction "1_1") (pintype "passive"))
    )
    (net (code "39") (name "Net-(AMP3-IP-)") (class "Default")
      (node (ref "AMP3") (pin "3") (pinfunction "IP-_3") (pintype "passive"))
      (node (ref "AMP3") (pin "4") (pinfunction "IP-1_4") (pintype "passive"))
      (node (ref "U$4") (pin "SWCOMMON") (pinfunction "SWCOMMON_SWCOMMON") (pintype "bidirectional"))
    )
    (net (code "40") (name "Net-(AMP3-VOUT)") (class "Default")
      (node (ref "AMP3") (pin "7") (pinfunction "VOUT_7") (pintype "output"))
      (node (ref "R11") (pin "2") (pinfunction "2_2") (pintype "passive"))
    )
    (net (code "41") (name "Net-(BUTTON1-Pad2)") (class "Default")
      (node (ref "BUTTON1") (pin "2") (pinfunction "2_2") (pintype "passive"))
      (node (ref "R7") (pin "1") (pinfunction "1_1") (pintype "passive"))
    )
    (net (code "42") (name "Net-(BUTTON2-Pad2)") (class "Default")
      (node (ref "BUTTON2") (pin "2") (pinfunction "2_2") (pintype "passive"))
      (node (ref "R20") (pin "1") (pinfunction "1_1") (pintype "passive"))
    )
    (net (code "43") (name "Net-(BUTTON3-Pad2)") (class "Default")
      (node (ref "BUTTON3") (pin "2") (pinfunction "2_2") (pintype "passive"))
      (node (ref "R22") (pin "1") (pinfunction "1_1") (pintype "passive"))
    )
    (net (code "44") (name "Net-(D3-PadA)") (class "Default")
      (node (ref "D3") (pin "A") (pinfunction "A_A") (pintype "passive"))
      (node (ref "D7") (pin "C") (pinfunction "C_C") (pintype "passive"))
      (node (ref "J9") (pin "2") (pinfunction "2_2") (pintype "passive"))
    )
    (net (code "45") (name "Net-(D5-PadA)") (class "Default")
      (node (ref "D5") (pin "A") (pinfunction "A_A") (pintype "passive"))
      (node (ref "D6") (pin "C") (pinfunction "C_C") (pintype "passive"))
      (node (ref "J9") (pin "1") (pinfunction "1_1") (pintype "passive"))
    )
    (net (code "46") (name "Net-(HCPL-7520-VIN+)") (class "Default")
      (node (ref "HCPL-7520") (pin "2") (pinfunction "VIN+_2") (pintype "power_in"))
      (node (ref "R15") (pin "2") (pinfunction "2_2") (pintype "passive"))
      (node (ref "R16") (pin "1") (pinfunction "1_1") (pintype "passive"))
    )
    (net (code "47") (name "Net-(IC3A-1D)") (class "Default")
      (node (ref "IC3") (pin "3") (pinfunction "1D_3") (pintype "input"))
      (node (ref "U1") (pin "12") (pinfunction "IO27_12") (pintype "bidirectional"))
    )
    (net (code "48") (name "Net-(IC3A-2D)") (class "Default")
      (node (ref "IC3") (pin "4") (pinfunction "2D_4") (pintype "input"))
      (node (ref "U1") (pin "11") (pinfunction "IO26_11") (pintype "bidirectional"))
    )
    (net (code "49") (name "Net-(IC3A-3D)") (class "Default")
      (node (ref "IC3") (pin "7") (pinfunction "3D_7") (pintype "input"))
      (node (ref "U1") (pin "10") (pinfunction "IO25_10") (pintype "bidirectional"))
    )
    (net (code "50") (name "Net-(IC3A-ENC)") (class "Default")
      (node (ref "IC3") (pin "11") (pinfunction "ENC_11") (pintype "input"))
      (node (ref "R17") (pin "1") (pinfunction "1_1") (pintype "passive"))
      (node (ref "U1") (pin "5") (pinfunction "SVN_5") (pintype "bidirectional"))
    )
    (net (code "51") (name "Net-(J3-Pad1)") (class "Default")
      (node (ref "J3") (pin "1") (pinfunction "1_1") (pintype "passive"))
      (node (ref "U$1") (pin "AC2") (pinfunction "AC2_AC2") (pintype "bidirectional"))
    )
    (net (code "52") (name "Net-(J3-Pad2)") (class "Default")
      (node (ref "J3") (pin "2") (pinfunction "2_2") (pintype "passive"))
      (node (ref "U$1") (pin "AC1") (pinfunction "AC1_AC1") (pintype "bidirectional"))
    )
    (net (code "53") (name "Net-(J4-Pad1)") (class "Default")
      (node (ref "J4") (pin "1") (pinfunction "1_1") (pintype "passive"))
      (node (ref "U$5") (pin "AC2") (pinfunction "AC2_AC2") (pintype "bidirectional"))
    )
    (net (code "54") (name "Net-(J4-Pad2)") (class "Default")
      (node (ref "J4") (pin "2") (pinfunction "2_2") (pintype "passive"))
      (node (ref "U$5") (pin "AC1") (pinfunction "AC1_AC1") (pintype "bidirectional"))
    )
    (net (code "55") (name "Net-(OK1-C)") (class "Default")
      (node (ref "OK1") (pin "2") (pinfunction "C_2") (pintype "passive"))
      (node (ref "R5") (pin "2") (pinfunction "2_2") (pintype "passive"))
    )
    (net (code "56") (name "Net-(OK1-EMIT)") (class "Default")
      (node (ref "OK1") (pin "3") (pinfunction "EMIT_3") (pintype "passive"))
      (node (ref "Q1") (pin "1") (pinfunction "G_1") (pintype "bidirectional"))
      (node (ref "R3") (pin "1") (pinfunction "1_1") (pintype "passive"))
    )
    (net (code "57") (name "Net-(OK2-C)") (class "Default")
      (node (ref "OK2") (pin "2") (pinfunction "C_2") (pintype "passive"))
      (node (ref "R10") (pin "2") (pinfunction "2_2") (pintype "passive"))
    )
    (net (code "58") (name "Net-(OK2-EMIT)") (class "Default")
      (node (ref "OK2") (pin "3") (pinfunction "EMIT_3") (pintype "passive"))
      (node (ref "Q2") (pin "1") (pinfunction "G_1") (pintype "bidirectional"))
      (node (ref "R8") (pin "1") (pinfunction "1_1") (pintype "passive"))
    )
    (net (code "59") (name "Net-(OK3-C)") (class "Default")
      (node (ref "OK3") (pin "2") (pinfunction "C_2") (pintype "passive"))
      (node (ref "R14") (pin "2") (pinfunction "2_2") (pintype "passive"))
    )
    (net (code "60") (name "Net-(OK3-EMIT)") (class "Default")
      (node (ref "OK3") (pin "3") (pinfunction "EMIT_3") (pintype "passive"))
      (node (ref "Q3") (pin "1") (pinfunction "G_1") (pintype "bidirectional"))
      (node (ref "R12") (pin "1") (pinfunction "1_1") (pintype "passive"))
    )
    (net (code "61") (name "Net-(Q1-D)") (class "Default")
      (node (ref "D4") (pin "A") (pinfunction "A_A") (pintype "passive"))
      (node (ref "Q1") (pin "3") (pinfunction "D_3") (pintype "bidirectional"))
      (node (ref "U$6") (pin "COIL0") (pinfunction "COIL0_COIL0") (pintype "bidirectional"))
      (node (ref "U$7") (pin "COIL0") (pinfunction "COIL0_COIL0") (pintype "bidirectional"))
    )
    (net (code "62") (name "Net-(Q2-D)") (class "Default")
      (node (ref "D1") (pin "A") (pinfunction "A_A") (pintype "passive"))
      (node (ref "Q2") (pin "3") (pinfunction "D_3") (pintype "bidirectional"))
      (node (ref "U$2") (pin "COIL0") (pinfunction "COIL0_COIL0") (pintype "bidirectional"))
      (node (ref "U$3") (pin "COIL0") (pinfunction "COIL0_COIL0") (pintype "bidirectional"))
    )
    (net (code "63") (name "Net-(Q3-D)") (class "Default")
      (node (ref "D2") (pin "A") (pinfunction "A_A") (pintype "passive"))
      (node (ref "Q3") (pin "3") (pinfunction "D_3") (pintype "bidirectional"))
      (node (ref "U$4") (pin "COIL0") (pinfunction "COIL0_COIL0") (pintype "bidirectional"))
      (node (ref "U$8") (pin "COIL0") (pinfunction "COIL0_COIL0") (pintype "bidirectional"))
    )
    (net (code "64") (name "Net-(Q4-D)") (class "Default")
      (node (ref "Q4") (pin "3") (pinfunction "D_3") (pintype "bidirectional"))
      (node (ref "R20") (pin "2") (pinfunction "2_2") (pintype "passive"))
    )
    (net (code "65") (name "Net-(Q5-D)") (class "Default")
      (node (ref "Q5") (pin "3") (pinfunction "D_3") (pintype "bidirectional"))
      (node (ref "R7") (pin "2") (pinfunction "2_2") (pintype "passive"))
    )
    (net (code "66") (name "Net-(Q6-D)") (class "Default")
      (node (ref "Q6") (pin "3") (pinfunction "D_3") (pintype "bidirectional"))
      (node (ref "R22") (pin "2") (pinfunction "2_2") (pintype "passive"))
    )
    (net (code "67") (name "Net-(RESET-P)") (class "Default")
      (node (ref "R1") (pin "1") (pinfunction "1_1") (pintype "passive"))
      (node (ref "RESET") (pin "3") (pinfunction "P_3") (pintype "passive"))
      (node (ref "RESET") (pin "4") (pinfunction "P1_4") (pintype "passive"))
      (node (ref "U1") (pin "3") (pinfunction "EN_3") (pintype "input"))
    )
    (net (code "68") (name "Net-(U1-IO12)") (class "Default")
      (node (ref "JTAG") (pin "3") (pinfunction "3_3") (pintype "passive"))
      (node (ref "U1") (pin "14") (pinfunction "IO12_14") (pintype "bidirectional"))
    )
    (net (code "69") (name "Net-(U1-IO13)") (class "Default")
      (node (ref "JTAG") (pin "2") (pinfunction "2_2") (pintype "passive"))
      (node (ref "U1") (pin "16") (pinfunction "IO13_16") (pintype "bidirectional"))
    )
    (net (code "70") (name "Net-(U1-IO14)") (class "Default")
      (node (ref "JTAG") (pin "4") (pinfunction "4_4") (pintype "passive"))
      (node (ref "U1") (pin "13") (pinfunction "IO14_13") (pintype "bidirectional"))
    )
    (net (code "71") (name "Net-(U1-IO15)") (class "Default")
      (node (ref "JTAG") (pin "1") (pinfunction "1_1") (pintype "passive"))
      (node (ref "U1") (pin "23") (pinfunction "IO15_23") (pintype "bidirectional"))
    )
    (net (code "72") (name "Net-(U1-U0RXD)") (class "Default")
      (node (ref "U1") (pin "34") (pinfunction "U0RXD_34") (pintype "bidirectional"))
      (node (ref "UART") (pin "3") (pinfunction "3_3") (pintype "passive"))
    )
    (net (code "73") (name "Net-(U1-U0TXD)") (class "Default")
      (node (ref "U1") (pin "35") (pinfunction "U0TXD_35") (pintype "bidirectional"))
      (node (ref "UART") (pin "2") (pinfunction "2_2") (pintype "passive"))
    )
    (net (code "74") (name "VCC") (class "Default")
      (node (ref "BUTTON1") (pin "1") (pinfunction "1_1") (pintype "passive"))
      (node (ref "BUTTON2") (pin "1") (pinfunction "1_1") (pintype "passive"))
      (node (ref "BUTTON3") (pin "1") (pinfunction "1_1") (pintype "passive"))
      (node (ref "C12") (pin "2") (pinfunction "2_2") (pintype "passive"))
      (node (ref "C2") (pin "1") (pinfunction "1_1") (pintype "passive"))
      (node (ref "C3") (pin "1") (pinfunction "1_1") (pintype "passive"))
      (node (ref "HCPL-7520") (pin "8") (pinfunction "VDD2_8") (pintype "power_in"))
      (node (ref "IC1") (pin "2") (pinfunction "VOUT_2") (pintype "output"))
      (node (ref "IC1") (pin "4") (pinfunction "VOUT_4") (pintype "output"))
      (node (ref "R1") (pin "2") (pinfunction "2_2") (pintype "passive"))
      (node (ref "R2") (pin "1") (pinfunction "1_1") (pintype "passive"))
      (node (ref "U1") (pin "2") (pinfunction "3V3_2") (pintype "power_in"))
      (node (ref "UART") (pin "4") (pinfunction "4_4") (pintype "passive"))
    )
    (net (code "75") (name "VDD") (class "Default")
      (node (ref "C11") (pin "2") (pinfunction "2_2") (pintype "passive"))
      (node (ref "D1") (pin "C") (pinfunction "C_C") (pintype "passive"))
      (node (ref "D2") (pin "C") (pinfunction "C_C") (pintype "passive"))
      (node (ref "D4") (pin "C") (pinfunction "C_C") (pintype "passive"))
      (node (ref "HCPL-7520") (pin "1") (pinfunction "VDD1_1") (pintype "power_in"))
      (node (ref "OK1") (pin "4") (pinfunction "COL_4") (pintype "passive"))
      (node (ref "OK2") (pin "4") (pinfunction "COL_4") (pintype "passive"))
      (node (ref "OK3") (pin "4") (pinfunction "COL_4") (pintype "passive"))
      (node (ref "U$2") (pin "COIL1") (pinfunction "COIL1_COIL1") (pintype "bidirectional"))
      (node (ref "U$3") (pin "COIL1") (pinfunction "COIL1_COIL1") (pintype "bidirectional"))
      (node (ref "U$4") (pin "COIL1") (pinfunction "COIL1_COIL1") (pintype "bidirectional"))
      (node (ref "U$5") (pin "+VO") (pinfunction "+VO_+VO") (pintype "bidirectional"))
      (node (ref "U$6") (pin "COIL1") (pinfunction "COIL1_COIL1") (pintype "bidirectional"))
      (node (ref "U$7") (pin "COIL1") (pinfunction "COIL1_COIL1") (pintype "bidirectional"))
      (node (ref "U$8") (pin "COIL1") (pinfunction "COIL1_COIL1") (pintype "bidirectional"))
    )
    (net (code "76") (name "VSS") (class "Default")
      (node (ref "4.5V_REG") (pin "5") (pinfunction "VOUT_5") (pintype "output"))
      (node (ref "AMP1") (pin "8") (pinfunction "VCC_8") (pintype "power_in"))
      (node (ref "AMP2") (pin "8") (pinfunction "VCC_8") (pintype "power_in"))
      (node (ref "AMP3") (pin "8") (pinfunction "VCC_8") (pintype "power_in"))
      (node (ref "C4") (pin "2") (pinfunction "2_2") (pintype "passive"))
      (node (ref "C5") (pin "1") (pinfunction "1_1") (pintype "passive"))
      (node (ref "C7") (pin "1") (pinfunction "1_1") (pintype "passive"))
      (node (ref "C9") (pin "1") (pinfunction "1_1") (pintype "passive"))
    )
    (net (code "77") (name "unconnected-(IC3A-4Q-Pad9)") (class "Default")
      (node (ref "IC3") (pin "9") (pinfunction "4Q_9") (pintype "tri_state"))
    )
    (net (code "78") (name "unconnected-(IC3A-5Q-Pad12)") (class "Default")
      (node (ref "IC3") (pin "12") (pinfunction "5Q_12") (pintype "tri_state"))
    )
    (net (code "79") (name "unconnected-(IC3A-6Q-Pad15)") (class "Default")
      (node (ref "IC3") (pin "15") (pinfunction "6Q_15") (pintype "tri_state"))
    )
    (net (code "80") (name "unconnected-(IC3A-7Q-Pad16)") (class "Default")
      (node (ref "IC3") (pin "16") (pinfunction "7Q_16") (pintype "tri_state"))
    )
    (net (code "81") (name "unconnected-(IC3A-8Q-Pad19)") (class "Default")
      (node (ref "IC3") (pin "19") (pinfunction "8Q_19") (pintype "tri_state"))
    )
    (net (code "82") (name "unconnected-(U$2-PadSWOPEN)") (class "Default")
      (node (ref "U$2") (pin "SWOPEN") (pinfunction "SWOPEN_SWOPEN") (pintype "bidirectional"))
    )
    (net (code "83") (name "unconnected-(U$3-PadSWOPEN)") (class "Default")
      (node (ref "U$3") (pin "SWOPEN") (pinfunction "SWOPEN_SWOPEN") (pintype "bidirectional"))
    )
    (net (code "84") (name "unconnected-(U$4-PadSWOPEN)") (class "Default")
      (node (ref "U$4") (pin "SWOPEN") (pinfunction "SWOPEN_SWOPEN") (pintype "bidirectional"))
    )
    (net (code "85") (name "unconnected-(U$6-PadSWOPEN)") (class "Default")
      (node (ref "U$6") (pin "SWOPEN") (pinfunction "SWOPEN_SWOPEN") (pintype "bidirectional"))
    )
    (net (code "86") (name "unconnected-(U$7-PadSWOPEN)") (class "Default")
      (node (ref "U$7") (pin "SWOPEN") (pinfunction "SWOPEN_SWOPEN") (pintype "bidirectional"))
    )
    (net (code "87") (name "unconnected-(U$8-PadSWOPEN)") (class "Default")
      (node (ref "U$8") (pin "SWOPEN") (pinfunction "SWOPEN_SWOPEN") (pintype "bidirectional"))
    )
    (net (code "88") (name "unconnected-(U1-CLK-Pad20)") (class "Default")
      (node (ref "U1") (pin "20") (pinfunction "CLK_20") (pintype "bidirectional"))
    )
    (net (code "89") (name "unconnected-(U1-CMD-Pad19)") (class "Default")
      (node (ref "U1") (pin "19") (pinfunction "CMD_19") (pintype "bidirectional"))
    )
    (net (code "90") (name "unconnected-(U1-IO4-Pad26)") (class "Default")
      (node (ref "U1") (pin "26") (pinfunction "IO4_26") (pintype "bidirectional"))
    )
    (net (code "91") (name "unconnected-(U1-IO22-Pad36)") (class "Default")
      (node (ref "U1") (pin "36") (pinfunction "IO22_36") (pintype "bidirectional"))
    )
    (net (code "92") (name "unconnected-(U1-IO23-Pad37)") (class "Default")
      (node (ref "U1") (pin "37") (pinfunction "IO23_37") (pintype "bidirectional"))
    )
    (net (code "93") (name "unconnected-(U1-SD0-Pad21)") (class "Default")
      (node (ref "U1") (pin "21") (pinfunction "SD0_21") (pintype "bidirectional"))
    )
    (net (code "94") (name "unconnected-(U1-SD1-Pad22)") (class "Default")
      (node (ref "U1") (pin "22") (pinfunction "SD1_22") (pintype "bidirectional"))
    )
    (net (code "95") (name "unconnected-(U1-SD2-Pad17)") (class "Default")
      (node (ref "U1") (pin "17") (pinfunction "SD2_17") (pintype "bidirectional"))
    )
    (net (code "96") (name "unconnected-(U1-SD3-Pad18)") (class "Default")
      (node (ref "U1") (pin "18") (pinfunction "SD3_18") (pintype "bidirectional"))
    )
    (net (code "97") (name "unconnected-(U1-SVP-Pad4)") (class "Default")
      (node (ref "U1") (pin "4") (pinfunction "SVP_4") (pintype "bidirectional"))
    )
  )
)
